# ld.net
KiCad netlist of a schematic drawn in EAGLE
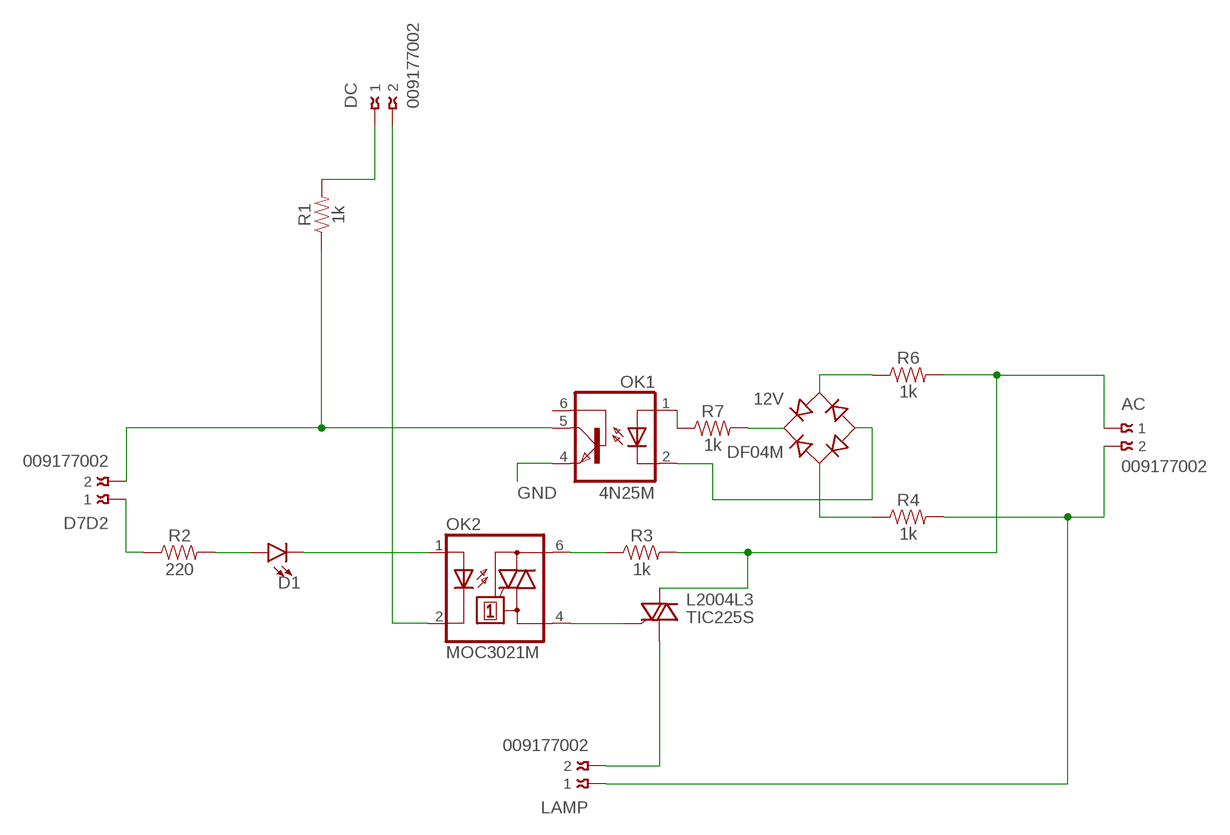
[diagram p0: schematic, sheet 1]

(export (version "E")
  (design (tool "Eeschema 10.0.6"))
  (components
    (comp (ref "AC")
      (value "009177002")
      (footprint "eagle-import:009177002")
      (fields (field (name "MPN") "009177002001006"))
      (libsource (lib "eagle-import") (part "00917?0027"))
    )
    (comp (ref "D1")
      (value "LED1206")
      (footprint "eagle-import:LED-1206")
      (libsource (lib "eagle-import") (part "LED1206"))
    )
    (comp (ref "D7D2")
      (value "009177002")
      (footprint "eagle-import:009177002")
      (fields (field (name "MPN") "009177002001006"))
      (libsource (lib "eagle-import") (part "00917?0027"))
    )
    (comp (ref "DC")
      (value "009177002")
      (footprint "eagle-import:009177002")
      (fields (field (name "MPN") "009177002001006"))
      (libsource (lib "eagle-import") (part "00917?0027"))
    )
    (comp (ref "DF04M")
      (value "12V")
      (footprint "eagle-import:B-DIL")
      (libsource (lib "eagle-import") (part "B-DIL"))
    )
    (comp (ref "L2004L3")
      (value "TIC225S")
      (footprint "eagle-import:TO220DS")
      (libsource (lib "eagle-import") (part "TIC225S"))
    )
    (comp (ref "LAMP")
      (value "009177002")
      (footprint "eagle-import:009177002")
      (fields (field (name "MPN") "009177002001006"))
      (libsource (lib "eagle-import") (part "00917?0027"))
    )
    (comp (ref "OK1")
      (value "4N25M")
      (footprint "eagle-import:DIL06")
      (fields (field (name "MPN") "4N25-M"))
      (libsource (lib "eagle-import") (part "4N?M25"))
    )
    (comp (ref "OK2")
      (value "MOC3021M")
      (footprint "eagle-import:DIL06")
      (fields (field (name "MF") "FAIRCHILD SEMICONDUCTOR") (field (name "MPN") "MOC3021-M"))
      (libsource (lib "eagle-import") (part "MOC30M21"))
    )
    (comp (ref "R1")
      (value "1k")
      (footprint "eagle-import:AXIAL-0.3")
      (libsource (lib "eagle-import") (part "1KOHM-HORIZ-1/4W-1%"))
    )
    (comp (ref "R2")
      (value "220")
      (footprint "eagle-import:0805")
      (libsource (lib "eagle-import") (part "0.75OHM-0805-1/4W-1%"))
    )
    (comp (ref "R3")
      (value "1k")
      (footprint "eagle-import:AXIAL-0.3")
      (libsource (lib "eagle-import") (part "1KOHM-HORIZ-1/4W-1%"))
    )
    (comp (ref "R4")
      (value "1k")
      (footprint "eagle-import:AXIAL-0.3")
      (libsource (lib "eagle-import") (part "1KOHM-HORIZ-1/4W-1%"))
    )
    (comp (ref "R6")
      (value "1k")
      (footprint "eagle-import:AXIAL-0.3")
      (libsource (lib "eagle-import") (part "1KOHM-HORIZ-1/4W-1%"))
    )
    (comp (ref "R7")
      (value "1k")
      (footprint "eagle-import:0805")
      (libsource (lib "eagle-import") (part "0.75OHM-0805-1/4W-1%"))
    )
  )
  (nets
    (net (code "1") (name "/GND") (class "Default")
      (node (ref "AC") (pin "2") (pinfunction "2_2") (pintype "passive"))
      (node (ref "LAMP") (pin "1") (pinfunction "1_1") (pintype "passive"))
      (node (ref "OK1") (pin "4") (pinfunction "EMI_4") (pintype "passive"))
      (node (ref "R4") (pin "P$2") (pinfunction "2_P$2") (pintype "passive"))
    )
    (net (code "2") (name "Net-(D1-PadA)") (class "Default")
      (node (ref "D1") (pin "A") (pinfunction "A_A") (pintype "passive"))
      (node (ref "R2") (pin "2") (pinfunction "2_2") (pintype "passive"))
    )
    (net (code "3") (name "Net-(D7D2-Pad1)") (class "Default")
      (node (ref "D7D2") (pin "1") (pinfunction "1_1") (pintype "passive"))
      (node (ref "R2") (pin "1") (pinfunction "1_1") (pintype "passive"))
    )
    (net (code "4") (name "Net-(DF04M-Pad+)") (class "Default")
      (node (ref "DF04M") (pin "+") (pinfunction "+_+") (pintype "passive"))
      (node (ref "R7") (pin "2") (pinfunction "2_2") (pintype "passive"))
    )
    (net (code "5") (name "Net-(L2004L3-PadA1)") (class "Default")
      (node (ref "L2004L3") (pin "A1") (pinfunction "A1_A1") (pintype "passive"))
      (node (ref "LAMP") (pin "2") (pinfunction "2_2") (pintype "passive"))
    )
    (net (code "6") (name "Net-(OK1-A)") (class "Default")
      (node (ref "OK1") (pin "1") (pinfunction "A_1") (pintype "passive"))
      (node (ref "R7") (pin "1") (pinfunction "1_1") (pintype "passive"))
    )
    (net (code "7") (name "Net-(OK1-C)") (class "Default")
      (node (ref "DF04M") (pin "-") (pinfunction "-_-") (pintype "passive"))
      (node (ref "OK1") (pin "2") (pinfunction "C_2") (pintype "passive"))
    )
    (net (code "8") (name "Net-(OK1-COL)") (class "Default")
      (node (ref "D7D2") (pin "2") (pinfunction "2_2") (pintype "passive"))
      (node (ref "OK1") (pin "5") (pinfunction "COL_5") (pintype "passive"))
      (node (ref "R1") (pin "P$1") (pinfunction "1_P$1") (pintype "passive"))
    )
    (net (code "9") (name "Net-(OK2-A)") (class "Default")
      (node (ref "D1") (pin "C") (pinfunction "C_C") (pintype "passive"))
      (node (ref "OK2") (pin "1") (pinfunction "A_1") (pintype "passive"))
    )
    (net (code "10") (name "Net-(OK2-A1)") (class "Default")
      (node (ref "L2004L3") (pin "G") (pinfunction "G_G") (pintype "passive"))
      (node (ref "OK2") (pin "4") (pinfunction "A1_4") (pintype "passive"))
    )
    (net (code "11") (name "Net-(OK2-A2)") (class "Default")
      (node (ref "OK2") (pin "6") (pinfunction "A2_6") (pintype "passive"))
      (node (ref "R3") (pin "P$1") (pinfunction "1_P$1") (pintype "passive"))
    )
    (net (code "12") (name "Net-(OK2-C)") (class "Default")
      (node (ref "DC") (pin "2") (pinfunction "2_2") (pintype "passive"))
      (node (ref "OK2") (pin "2") (pinfunction "C_2") (pintype "passive"))
    )
    (net (code "13") (name "Net-(R1-2)") (class "Default")
      (node (ref "DC") (pin "1") (pinfunction "1_1") (pintype "passive"))
      (node (ref "R1") (pin "P$2") (pinfunction "2_P$2") (pintype "passive"))
    )
    (net (code "14") (name "Net-(R3-2)") (class "Default")
      (node (ref "AC") (pin "1") (pinfunction "1_1") (pintype "passive"))
      (node (ref "L2004L3") (pin "A2") (pinfunction "A2_A2") (pintype "passive"))
      (node (ref "R3") (pin "P$2") (pinfunction "2_P$2") (pintype "passive"))
      (node (ref "R6") (pin "P$2") (pinfunction "2_P$2") (pintype "passive"))
    )
    (net (code "15") (name "Net-(R4-1)") (class "Default")
      (node (ref "DF04M") (pin "AC1") (pinfunction "AC1_AC1") (pintype "passive"))
      (node (ref "R4") (pin "P$1") (pinfunction "1_P$1") (pintype "passive"))
    )
    (net (code "16") (name "Net-(R6-1)") (class "Default")
      (node (ref "DF04M") (pin "AC2") (pinfunction "AC2_AC2") (pintype "passive"))
      (node (ref "R6") (pin "P$1") (pinfunction "1_P$1") (pintype "passive"))
    )
    (net (code "17") (name "unconnected-(OK1-BAS-Pad6)") (class "Default")
      (node (ref "OK1") (pin "6") (pinfunction "BAS_6") (pintype "passive"))
    )
  )
)
